# logic.net
KiCad netlist of a schematic drawn in Altium Designer
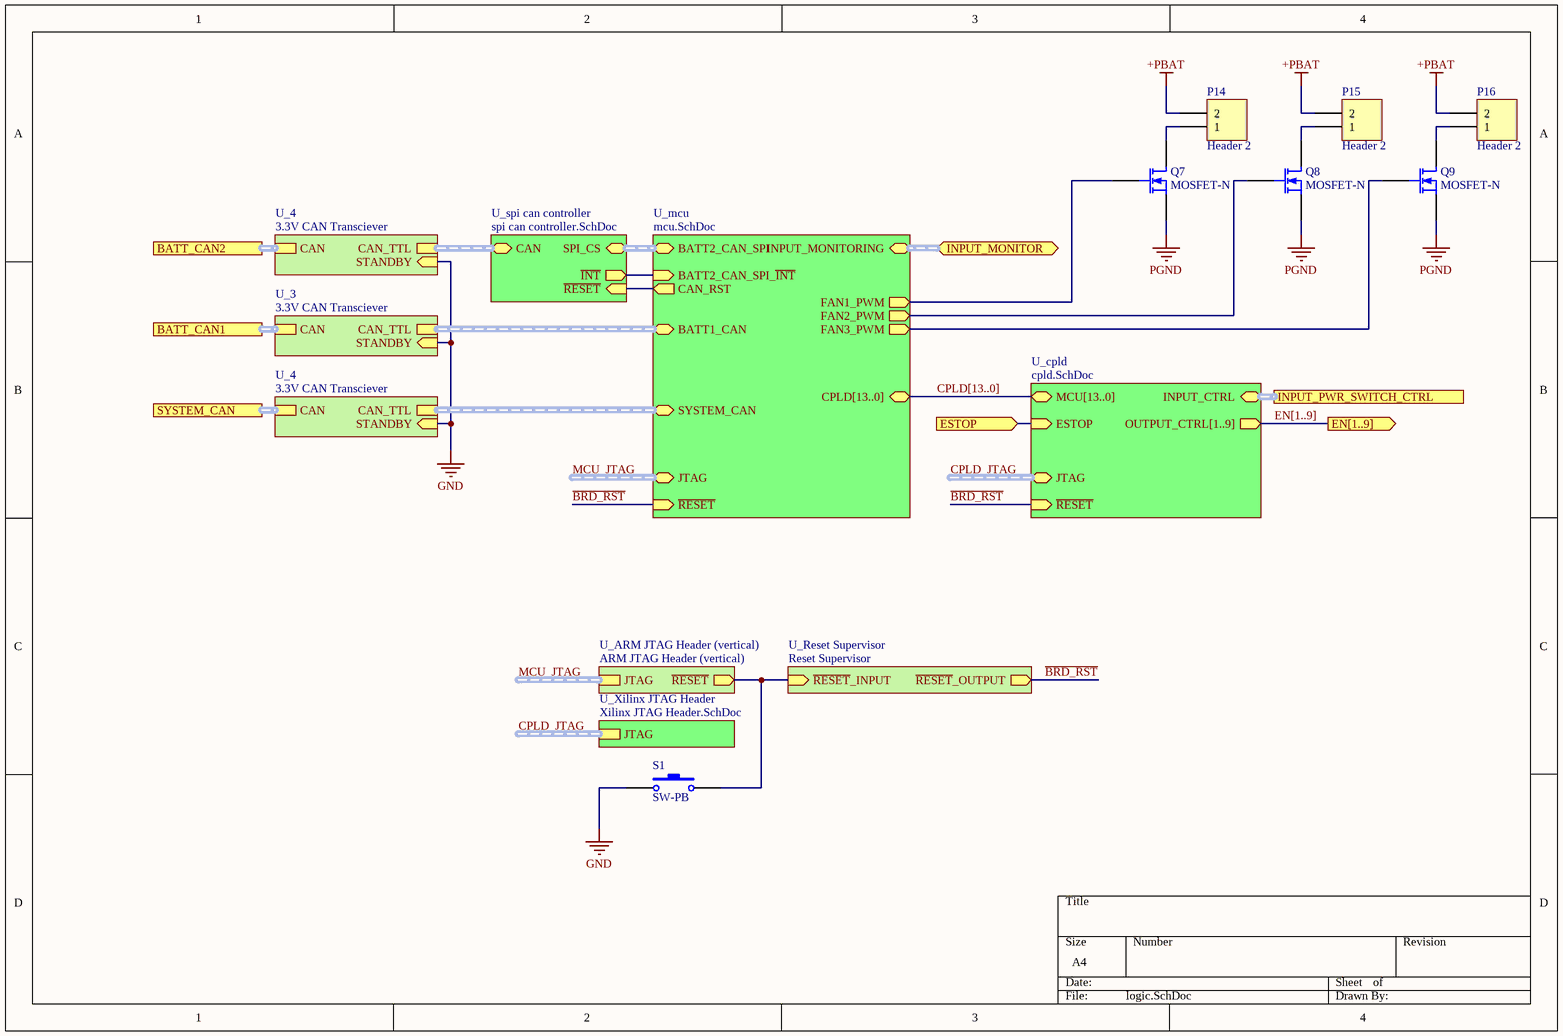
[diagram p0: logic.SchDoc]

(export (version "E")
  (design (tool "Eeschema 10.0.6"))
  (components
    (comp (ref "P14")
      (value "Header 2")
      (footprint "HDR1X2")
      (description "Header, 2-Pin")
      (fields (field (name "PUBLISHER") "Altium Limited"))
      (libsource (lib "Miscellaneous Connectors") (part "Header 2"))
    )
    (comp (ref "P15")
      (value "Header 2")
      (footprint "HDR1X2")
      (description "Header, 2-Pin")
      (fields (field (name "PUBLISHER") "Altium Limited"))
      (libsource (lib "Miscellaneous Connectors") (part "Header 2"))
    )
    (comp (ref "P16")
      (value "Header 2")
      (footprint "HDR1X2")
      (description "Header, 2-Pin")
      (fields (field (name "PUBLISHER") "Altium Limited"))
      (libsource (lib "Miscellaneous Connectors") (part "Header 2"))
    )
    (comp (ref "Q7")
      (value "MOSFET-N")
      (footprint "TSM2306CX")
      (description "N-Channel MOSFET")
      (fields (field (name "PUBLISHER") "Altium Limited"))
      (libsource (lib "Miscellaneous Devices") (part "MOSFET-N"))
    )
    (comp (ref "Q8")
      (value "MOSFET-N")
      (footprint "TSM2306CX")
      (description "N-Channel MOSFET")
      (fields (field (name "PUBLISHER") "Altium Limited"))
      (libsource (lib "Miscellaneous Devices") (part "MOSFET-N"))
    )
    (comp (ref "Q9")
      (value "MOSFET-N")
      (footprint "TSM2306CX")
      (description "N-Channel MOSFET")
      (fields (field (name "PUBLISHER") "Altium Limited"))
      (libsource (lib "Miscellaneous Devices") (part "MOSFET-N"))
    )
    (comp (ref "S1")
      (value "SW-PB")
      (footprint "DTSM-32S-B")
      (description "Switch")
      (fields (field (name "PUBLISHER") "Altium Limited"))
      (libsource (lib "Miscellaneous Devices") (part "SW-PB"))
    )
  )
  (nets
    (net (code "31") (name "+PBAT") (class "Default")
      (node (ref "P14") (pin "2") (pinfunction "2_2") (pintype "passive"))
      (node (ref "P15") (pin "2") (pinfunction "2_2") (pintype "passive"))
      (node (ref "P16") (pin "2") (pinfunction "2_2") (pintype "passive"))
    )
    (net (code "42") (name "/FAN1_PWM") (class "Default")
      (node (ref "Q7") (pin "2") (pinfunction "G_2") (pintype "passive"))
    )
    (net (code "43") (name "/FAN2_PWM") (class "Default")
      (node (ref "Q8") (pin "2") (pinfunction "G_2") (pintype "passive"))
    )
    (net (code "44") (name "/FAN3_PWM") (class "Default")
      (node (ref "Q9") (pin "2") (pinfunction "G_2") (pintype "passive"))
    )
    (net (code "52") (name "/~{RESET}") (class "Default")
      (node (ref "S1") (pin "2") (pinfunction "2_2") (pintype "passive"))
    )
    (net (code "53") (name "GND") (class "Default")
      (node (ref "S1") (pin "1") (pinfunction "1_1") (pintype "passive"))
    )
    (net (code "54") (name "Net-(Q7-D)") (class "Default")
      (node (ref "P14") (pin "1") (pinfunction "1_1") (pintype "passive"))
      (node (ref "Q7") (pin "1") (pinfunction "D_1") (pintype "passive"))
    )
    (net (code "55") (name "Net-(Q8-D)") (class "Default")
      (node (ref "P15") (pin "1") (pinfunction "1_1") (pintype "passive"))
      (node (ref "Q8") (pin "1") (pinfunction "D_1") (pintype "passive"))
    )
    (net (code "56") (name "Net-(Q9-D)") (class "Default")
      (node (ref "P16") (pin "1") (pinfunction "1_1") (pintype "passive"))
      (node (ref "Q9") (pin "1") (pinfunction "D_1") (pintype "passive"))
    )
    (net (code "57") (name "PGND") (class "Default")
      (node (ref "Q7") (pin "3") (pinfunction "S_3") (pintype "passive"))
      (node (ref "Q8") (pin "3") (pinfunction "S_3") (pintype "passive"))
      (node (ref "Q9") (pin "3") (pinfunction "S_3") (pintype "passive"))
    )
  )
)
